# sw_receive.net
KiCad netlist of a schematic drawn in Altium Designer
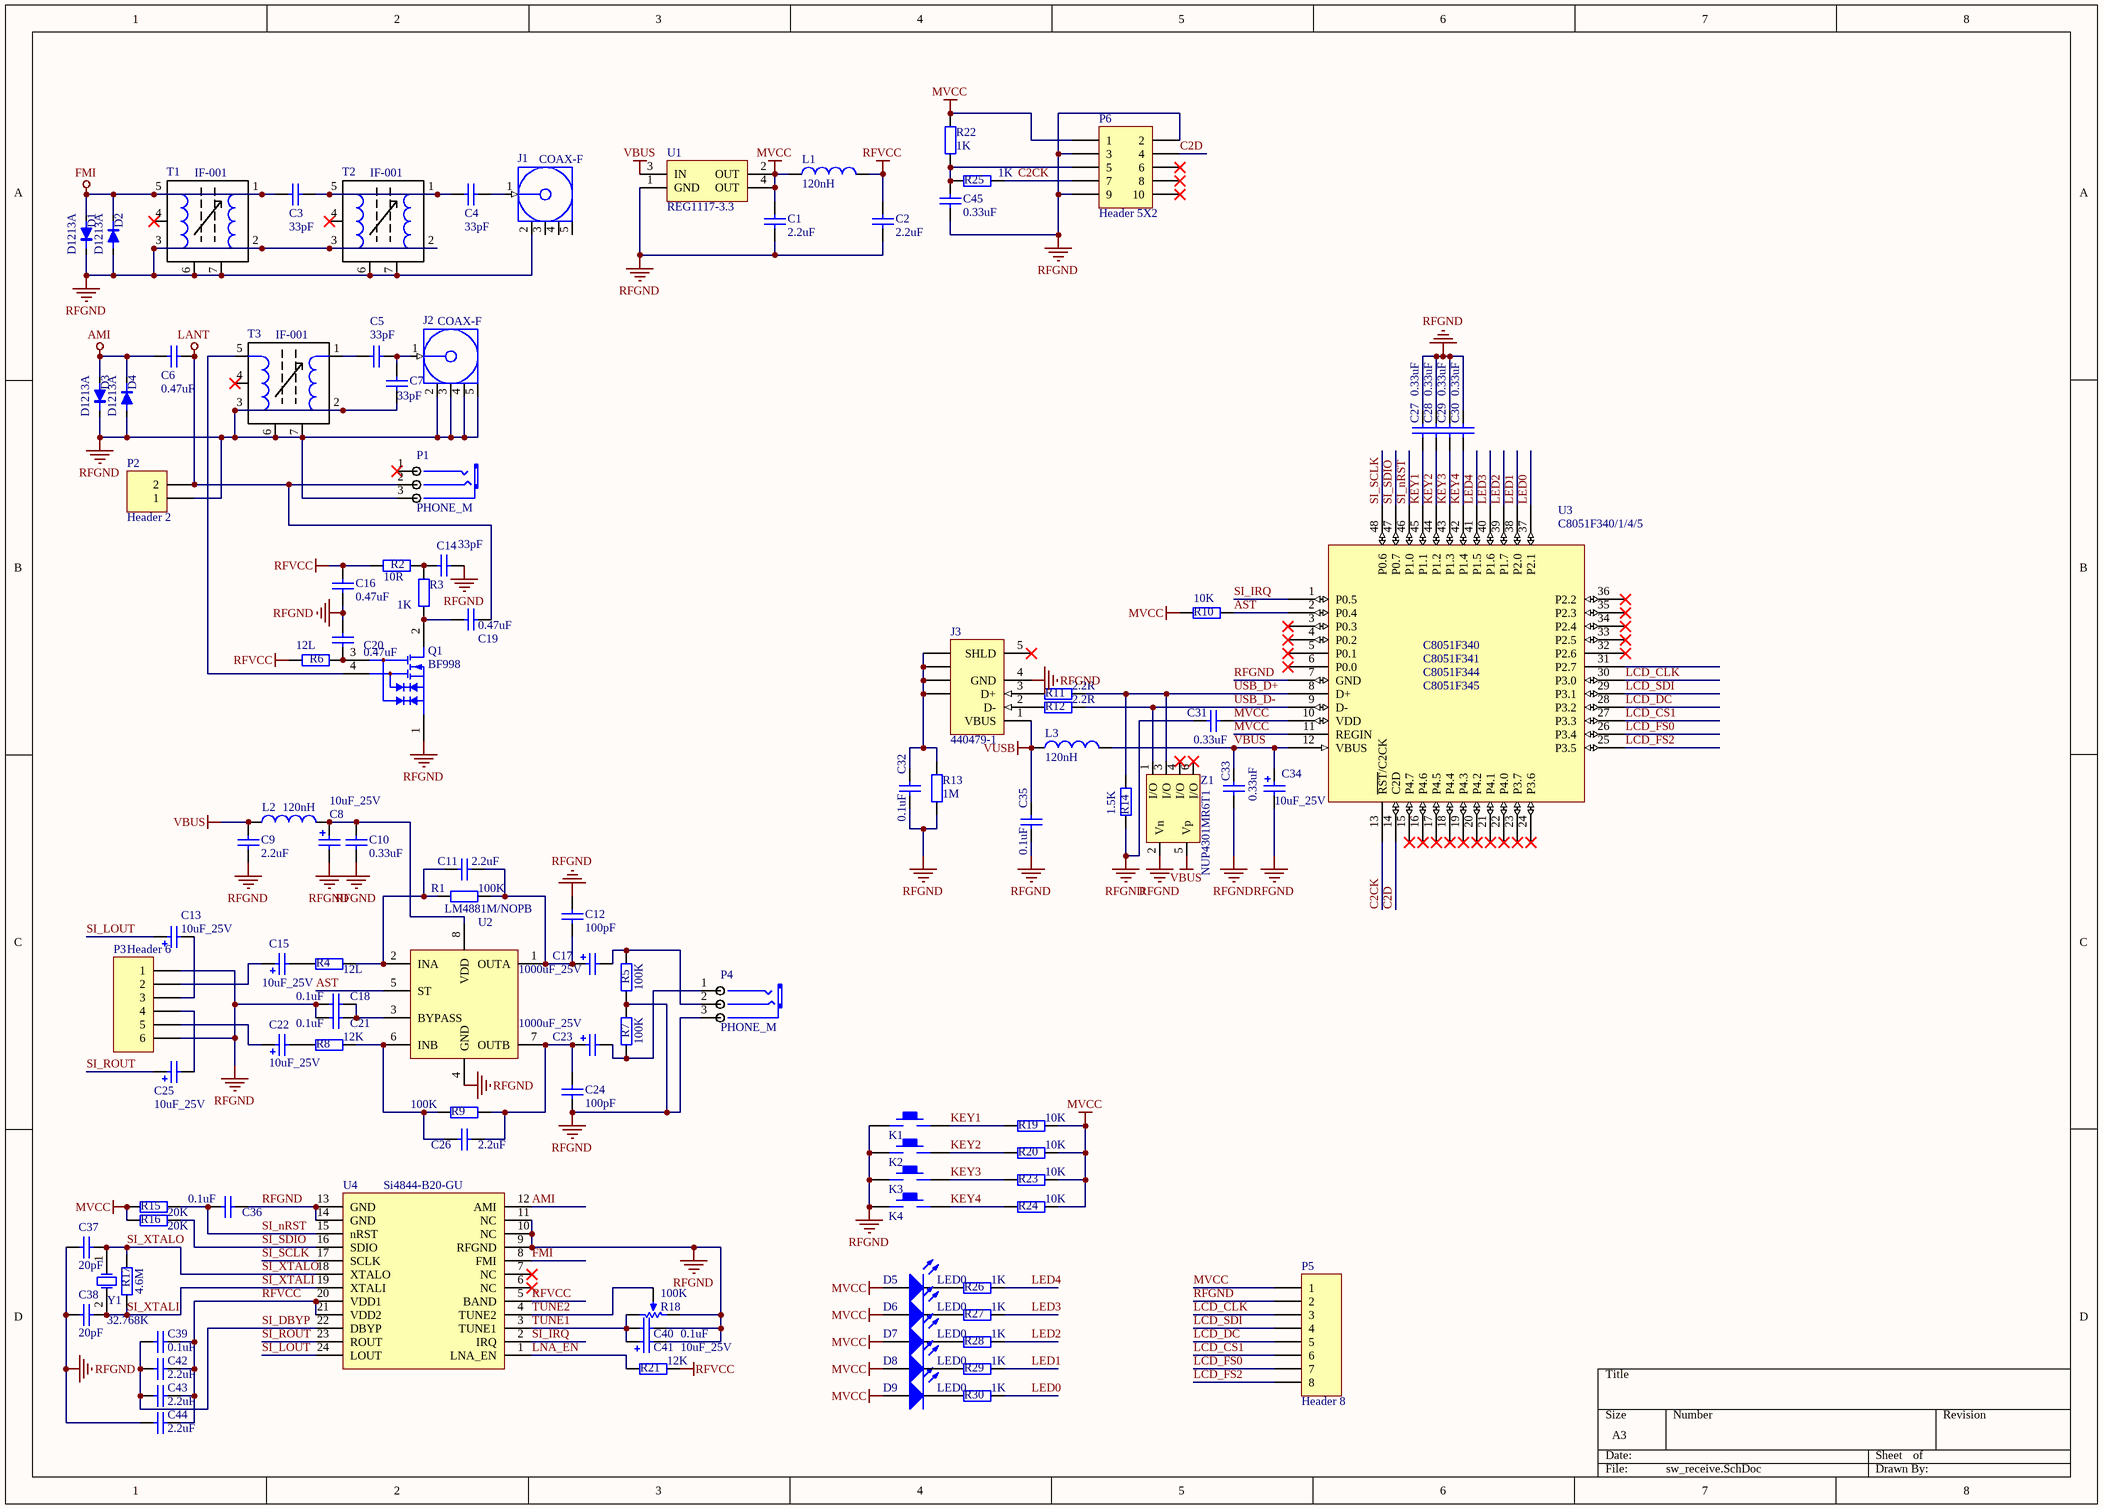
[diagram p0: sw_receive.SchDoc]

(export (version "E")
  (design (tool "Eeschema 10.0.6"))
  (components
    (comp (ref "C1")
      (value "2.2uF")
      (footprint "0805C")
      (description "Capacitor")
      (fields (field (name "PUBLISHER") "Altium Limited"))
      (libsource (lib "Miscellaneous Devices") (part "Cap"))
    )
    (comp (ref "C2")
      (value "2.2uF")
      (footprint "0805C")
      (description "Capacitor")
      (fields (field (name "PUBLISHER") "Altium Limited"))
      (libsource (lib "Miscellaneous Devices") (part "Cap"))
    )
    (comp (ref "C3")
      (value "33pF")
      (footprint "0805C")
      (description "Capacitor")
      (fields (field (name "PUBLISHER") "Altium Limited"))
      (libsource (lib "Miscellaneous Devices") (part "Cap"))
    )
    (comp (ref "C4")
      (value "33pF")
      (footprint "0805C")
      (description "Capacitor")
      (fields (field (name "PUBLISHER") "Altium Limited"))
      (libsource (lib "Miscellaneous Devices") (part "Cap"))
    )
    (comp (ref "C5")
      (value "33pF")
      (footprint "0805C")
      (description "Capacitor")
      (fields (field (name "PUBLISHER") "Altium Limited"))
      (libsource (lib "Miscellaneous Devices") (part "Cap"))
    )
    (comp (ref "C6")
      (value "0.47uF")
      (footprint "0805C")
      (description "Capacitor")
      (fields (field (name "PUBLISHER") "Altium Limited"))
      (libsource (lib "Miscellaneous Devices") (part "Cap"))
    )
    (comp (ref "C7")
      (value "33pF")
      (footprint "0805C")
      (description "Capacitor")
      (fields (field (name "PUBLISHER") "Altium Limited"))
      (libsource (lib "Miscellaneous Devices") (part "Cap"))
    )
    (comp (ref "C8")
      (value "10uF_25V")
      (footprint "RB2.5-6.3")
      (description "Polarized Capacitor (Axial)")
      (fields (field (name "PUBLISHER") "Altium Limited"))
      (libsource (lib "") (part "Cap Pol2_1"))
    )
    (comp (ref "C9")
      (value "2.2uF")
      (footprint "0805C")
      (description "Capacitor")
      (fields (field (name "PUBLISHER") "Altium Limited"))
      (libsource (lib "Miscellaneous Devices") (part "Cap"))
    )
    (comp (ref "C10")
      (value "0.33uF")
      (footprint "0805C")
      (description "Capacitor")
      (fields (field (name "PUBLISHER") "Altium Limited"))
      (libsource (lib "Miscellaneous Devices") (part "Cap"))
    )
    (comp (ref "C11")
      (value "2.2uF")
      (footprint "0805C")
      (description "Capacitor")
      (fields (field (name "PUBLISHER") "Altium Limited"))
      (libsource (lib "Miscellaneous Devices") (part "Cap"))
    )
    (comp (ref "C12")
      (value "100pF")
      (footprint "0805C")
      (description "Capacitor")
      (fields (field (name "PUBLISHER") "Altium Limited"))
      (libsource (lib "Miscellaneous Devices") (part "Cap"))
    )
    (comp (ref "C13")
      (value "10uF_25V")
      (footprint "RB2-5")
      (description "Polarized Capacitor (Axial)")
      (fields (field (name "PUBLISHER") "Altium Limited"))
      (libsource (lib "Miscellaneous Devices") (part "Cap Pol2"))
    )
    (comp (ref "C14")
      (value "33pF")
      (footprint "0805C")
      (description "Capacitor")
      (fields (field (name "PUBLISHER") "Altium Limited"))
      (libsource (lib "Miscellaneous Devices") (part "Cap"))
    )
    (comp (ref "C15")
      (value "10uF_25V")
      (footprint "RB2-5")
      (description "Polarized Capacitor (Axial)")
      (fields (field (name "PUBLISHER") "Altium Limited"))
      (libsource (lib "Miscellaneous Devices") (part "Cap Pol2"))
    )
    (comp (ref "C16")
      (value "0.47uF")
      (footprint "0805C")
      (description "Capacitor")
      (fields (field (name "PUBLISHER") "Altium Limited"))
      (libsource (lib "Miscellaneous Devices") (part "Cap"))
    )
    (comp (ref "C17")
      (value "1000uF_25V")
      (footprint "RB3.5-8")
      (description "Polarized Capacitor (Axial)")
      (fields (field (name "PUBLISHER") "Altium Limited"))
      (libsource (lib "Miscellaneous Devices") (part "Cap Pol2"))
    )
    (comp (ref "C18")
      (value "0.1uF")
      (footprint "CAPC3225L")
      (description "Capacitor")
      (fields (field (name "PUBLISHER") "Altium Limited"))
      (libsource (lib "Miscellaneous Devices") (part "Cap"))
    )
    (comp (ref "C19")
      (value "0.47uF")
      (footprint "0805C")
      (description "Capacitor")
      (fields (field (name "PUBLISHER") "Altium Limited"))
      (libsource (lib "Miscellaneous Devices") (part "Cap"))
    )
    (comp (ref "C20")
      (value "0.47uF")
      (footprint "0805C")
      (description "Capacitor")
      (fields (field (name "PUBLISHER") "Altium Limited"))
      (libsource (lib "Miscellaneous Devices") (part "Cap"))
    )
    (comp (ref "C21")
      (value "0.1uF")
      (footprint "0805C")
      (description "Capacitor")
      (fields (field (name "PUBLISHER") "Altium Limited"))
      (libsource (lib "Miscellaneous Devices") (part "Cap"))
    )
    (comp (ref "C22")
      (value "10uF_25V")
      (footprint "RB2-5")
      (description "Polarized Capacitor (Axial)")
      (fields (field (name "PUBLISHER") "Altium Limited"))
      (libsource (lib "Miscellaneous Devices") (part "Cap Pol2"))
    )
    (comp (ref "C23")
      (value "1000uF_25V")
      (footprint "RB3.5-8")
      (description "Polarized Capacitor (Axial)")
      (fields (field (name "PUBLISHER") "Altium Limited"))
      (libsource (lib "Miscellaneous Devices") (part "Cap Pol2"))
    )
    (comp (ref "C24")
      (value "100pF")
      (footprint "0805C")
      (description "Capacitor")
      (fields (field (name "PUBLISHER") "Altium Limited"))
      (libsource (lib "Miscellaneous Devices") (part "Cap"))
    )
    (comp (ref "C25")
      (value "10uF_25V")
      (footprint "RB2-5")
      (description "Polarized Capacitor (Axial)")
      (fields (field (name "PUBLISHER") "Altium Limited"))
      (libsource (lib "Miscellaneous Devices") (part "Cap Pol2"))
    )
    (comp (ref "C26")
      (value "2.2uF")
      (footprint "0805C")
      (description "Capacitor")
      (fields (field (name "PUBLISHER") "Altium Limited"))
      (libsource (lib "Miscellaneous Devices") (part "Cap"))
    )
    (comp (ref "C27")
      (value "0.33uF")
      (footprint "0805C")
      (description "Capacitor")
      (fields (field (name "PUBLISHER") "Altium Limited"))
      (libsource (lib "Miscellaneous Devices") (part "Cap"))
    )
    (comp (ref "C28")
      (value "0.33uF")
      (footprint "0805C")
      (description "Capacitor")
      (fields (field (name "PUBLISHER") "Altium Limited"))
      (libsource (lib "Miscellaneous Devices") (part "Cap"))
    )
    (comp (ref "C29")
      (value "0.33uF")
      (footprint "0805C")
      (description "Capacitor")
      (fields (field (name "PUBLISHER") "Altium Limited"))
      (libsource (lib "Miscellaneous Devices") (part "Cap"))
    )
    (comp (ref "C30")
      (value "0.33uF")
      (footprint "0805C")
      (description "Capacitor")
      (fields (field (name "PUBLISHER") "Altium Limited"))
      (libsource (lib "Miscellaneous Devices") (part "Cap"))
    )
    (comp (ref "C31")
      (value "0.33uF")
      (footprint "0805C")
      (description "Capacitor")
      (fields (field (name "PUBLISHER") "Altium Limited"))
      (libsource (lib "Miscellaneous Devices") (part "Cap"))
    )
    (comp (ref "C32")
      (value "0.1uF")
      (footprint "0805C")
      (description "Capacitor")
      (fields (field (name "PUBLISHER") "Altium Limited"))
      (libsource (lib "Miscellaneous Devices") (part "Cap"))
    )
    (comp (ref "C33")
      (value "0.33uF")
      (footprint "0805C")
      (description "Capacitor")
      (fields (field (name "PUBLISHER") "Altium Limited"))
      (libsource (lib "Miscellaneous Devices") (part "Cap"))
    )
    (comp (ref "C34")
      (value "10uF_25V")
      (footprint "RB2.5-6.3")
      (description "Polarized Capacitor (Axial)")
      (fields (field (name "PUBLISHER") "Altium Limited"))
      (libsource (lib "") (part "Cap Pol2_1"))
    )
    (comp (ref "C35")
      (value "0.1uF")
      (footprint "0805C")
      (description "Capacitor")
      (fields (field (name "PUBLISHER") "Altium Limited"))
      (libsource (lib "Miscellaneous Devices") (part "Cap"))
    )
    (comp (ref "C36")
      (value "0.1uF")
      (footprint "0805C")
      (description "Capacitor")
      (fields (field (name "PUBLISHER") "Altium Limited"))
      (libsource (lib "Miscellaneous Devices") (part "Cap"))
    )
    (comp (ref "C37")
      (value "20pF")
      (footprint "0805C")
      (description "Capacitor")
      (fields (field (name "PUBLISHER") "Altium Limited"))
      (libsource (lib "Miscellaneous Devices") (part "Cap"))
    )
    (comp (ref "C38")
      (value "20pF")
      (footprint "0805C")
      (description "Capacitor")
      (fields (field (name "PUBLISHER") "Altium Limited"))
      (libsource (lib "Miscellaneous Devices") (part "Cap"))
    )
    (comp (ref "C39")
      (value "0.1uF")
      (footprint "0805C")
      (description "Capacitor")
      (fields (field (name "PUBLISHER") "Altium Limited"))
      (libsource (lib "Miscellaneous Devices") (part "Cap"))
    )
    (comp (ref "C40")
      (value "0.1uF")
      (footprint "0805C")
      (description "Capacitor")
      (fields (field (name "PUBLISHER") "Altium Limited"))
      (libsource (lib "Miscellaneous Devices") (part "Cap"))
    )
    (comp (ref "C41")
      (value "10uF_25V")
      (footprint "RB2.5-6.3")
      (description "Polarized Capacitor (Axial)")
      (fields (field (name "PUBLISHER") "Altium Limited"))
      (libsource (lib "Miscellaneous Devices") (part "Cap Pol2"))
    )
    (comp (ref "C42")
      (value "2.2uF")
      (footprint "CAPC3225L")
      (description "Capacitor")
      (fields (field (name "PUBLISHER") "Altium Limited"))
      (libsource (lib "Miscellaneous Devices") (part "Cap"))
    )
    (comp (ref "C43")
      (value "2.2uF")
      (footprint "CAPC3225L")
      (description "Capacitor")
      (fields (field (name "PUBLISHER") "Altium Limited"))
      (libsource (lib "Miscellaneous Devices") (part "Cap"))
    )
    (comp (ref "C44")
      (value "2.2uF")
      (footprint "CAPC3225L")
      (description "Capacitor")
      (fields (field (name "PUBLISHER") "Altium Limited"))
      (libsource (lib "Miscellaneous Devices") (part "Cap"))
    )
    (comp (ref "C45")
      (value "0.33uF")
      (footprint "0805C")
      (description "Capacitor")
      (fields (field (name "PUBLISHER") "Altium Limited"))
      (libsource (lib "Miscellaneous Devices") (part "Cap"))
    )
    (comp (ref "D1") (value "D1213A") (footprint "SOD-323") (libsource (lib "常用元件库") (part "DIODE1")))
    (comp (ref "D2") (value "D1213A") (footprint "SOD-323") (libsource (lib "常用元件库") (part "DIODE1")))
    (comp (ref "D3") (value "D1213A") (footprint "SOD-323") (libsource (lib "常用元件库") (part "DIODE1")))
    (comp (ref "D4") (value "D1213A") (footprint "SOD-323") (libsource (lib "常用元件库") (part "DIODE1")))
    (comp (ref "D5")
      (value "LED0")
      (footprint "LEDLight")
      (description "Typical INFRARED GaAs LED")
      (fields (field (name "PUBLISHER") "Altium Limited"))
      (libsource (lib "Miscellaneous Devices") (part "LED0"))
    )
    (comp (ref "D6")
      (value "LED0")
      (footprint "LEDLight")
      (description "Typical INFRARED GaAs LED")
      (fields (field (name "PUBLISHER") "Altium Limited"))
      (libsource (lib "Miscellaneous Devices") (part "LED0"))
    )
    (comp (ref "D7")
      (value "LED0")
      (footprint "LEDLight")
      (description "Typical INFRARED GaAs LED")
      (fields (field (name "PUBLISHER") "Altium Limited"))
      (libsource (lib "Miscellaneous Devices") (part "LED0"))
    )
    (comp (ref "D8")
      (value "LED0")
      (footprint "LEDLight")
      (description "Typical INFRARED GaAs LED")
      (fields (field (name "PUBLISHER") "Altium Limited"))
      (libsource (lib "Miscellaneous Devices") (part "LED0"))
    )
    (comp (ref "D9")
      (value "LED0")
      (footprint "LEDLight")
      (description "Typical INFRARED GaAs LED")
      (fields (field (name "PUBLISHER") "Altium Limited"))
      (libsource (lib "Miscellaneous Devices") (part "LED0"))
    )
    (comp (ref "J1")
      (value "COAX-F")
      (footprint "MCX5.08-H5")
      (fields (field (name "PUBLISHER") "Altium Limited"))
      (libsource (lib "Miscellaneous Connectors") (part "COAX-F"))
    )
    (comp (ref "J2")
      (value "COAX-F")
      (footprint "MCX5.08-H5")
      (fields (field (name "PUBLISHER") "Altium Limited"))
      (libsource (lib "Miscellaneous Connectors") (part "COAX-F"))
    )
    (comp (ref "J3")
      (value "440479-1")
      (footprint "440479")
      (description "USB 2.0, Right Angle, SMT, AB Type, Receptacle, 5 Position, Black")
      (fields (field (name "PUBLISHER") "Altium Limited"))
      (libsource (lib "AMP Serial Bus USB") (part "440479-1"))
    )
    (comp (ref "K1") (value "KEY_M") (footprint "KEY_M") (libsource (lib "战舰STM32开发板底板封装库") (part "KEY_M")))
    (comp (ref "K2") (value "KEY_M") (footprint "KEY_M") (libsource (lib "战舰STM32开发板底板封装库") (part "KEY_M")))
    (comp (ref "K3") (value "KEY_M") (footprint "KEY_M") (libsource (lib "战舰STM32开发板底板封装库") (part "KEY_M")))
    (comp (ref "K4") (value "KEY_M") (footprint "KEY_M") (libsource (lib "战舰STM32开发板底板封装库") (part "KEY_M")))
    (comp (ref "L1")
      (value "120nH")
      (footprint "0805R")
      (description "Inductor")
      (fields (field (name "PUBLISHER") "Altium Limited"))
      (libsource (lib "Miscellaneous Devices") (part "Inductor"))
    )
    (comp (ref "L2")
      (value "120nH")
      (footprint "0805R")
      (description "Inductor")
      (fields (field (name "PUBLISHER") "Altium Limited"))
      (libsource (lib "Miscellaneous Devices") (part "Inductor"))
    )
    (comp (ref "L3")
      (value "120nH")
      (footprint "3225[1210]")
      (description "Inductor")
      (fields (field (name "PUBLISHER") "Altium Limited"))
      (libsource (lib "Miscellaneous Devices") (part "Inductor"))
    )
    (comp (ref "P1")
      (value "PHONE_M")
      (footprint "PHONE_ST")
      (libsource (lib "战舰STM32开发板底板封装库") (part "PHONE_M"))
    )
    (comp (ref "P2")
      (value "Header 2")
      (footprint "2510-2")
      (description "Header, 2-Pin")
      (fields (field (name "PUBLISHER") "Altium Limited"))
      (libsource (lib "Miscellaneous Connectors") (part "Header 2"))
    )
    (comp (ref "P3")
      (value "Header 6")
      (footprint "RK097")
      (description "Header, 6-Pin")
      (fields (field (name "PUBLISHER") "Altium Limited"))
      (libsource (lib "Miscellaneous Connectors") (part "Header 6"))
    )
    (comp (ref "P4")
      (value "PHONE_M")
      (footprint "PHONE_ST")
      (libsource (lib "战舰STM32开发板底板封装库") (part "PHONE_M"))
    )
    (comp (ref "P5")
      (value "Header 8")
      (footprint "HDR1X8")
      (description "Header, 8-Pin")
      (fields (field (name "PUBLISHER") "Altium Limited"))
      (libsource (lib "Miscellaneous Connectors") (part "Header 8"))
    )
    (comp (ref "P6")
      (value "Header 5X2")
      (footprint "FKV10SN")
      (description "Header, 5-Pin, Dual row")
      (fields (field (name "PUBLISHER") "Altium Limited"))
      (libsource (lib "Miscellaneous Connectors") (part "Header 5X2"))
    )
    (comp (ref "Q1")
      (value "BF998")
      (footprint "SOT143")
      (description "Silicon N-channel Dual-gate MOSFET")
      (fields (field (name "PUBLISHER") "Altium Limited"))
      (libsource (lib "Philips Discrete MOSFET - Low Power") (part "BF998"))
    )
    (comp (ref "R1")
      (value "100K")
      (footprint "0805R")
      (description "Resistor")
      (fields (field (name "PUBLISHER") "Altium Limited"))
      (libsource (lib "") (part "Res2_2"))
    )
    (comp (ref "R2")
      (value "10R")
      (footprint "0805R")
      (description "Resistor")
      (fields (field (name "PUBLISHER") "Altium Limited"))
      (libsource (lib "") (part "Res2_1"))
    )
    (comp (ref "R3")
      (value "1K")
      (footprint "0805R")
      (description "Resistor")
      (fields (field (name "PUBLISHER") "Altium Limited"))
      (libsource (lib "Miscellaneous Devices") (part "Res2"))
    )
    (comp (ref "R4")
      (value "12L")
      (footprint "0805R")
      (description "Resistor")
      (fields (field (name "PUBLISHER") "Altium Limited"))
      (libsource (lib "") (part "Res2_2"))
    )
    (comp (ref "R5")
      (value "100K")
      (footprint "0805R")
      (description "Resistor")
      (fields (field (name "PUBLISHER") "Altium Limited"))
      (libsource (lib "") (part "Res2_1"))
    )
    (comp (ref "R6")
      (value "12L")
      (footprint "0805R")
      (description "Resistor")
      (fields (field (name "PUBLISHER") "Altium Limited"))
      (libsource (lib "") (part "Res2_1"))
    )
    (comp (ref "R7")
      (value "100K")
      (footprint "0805R")
      (description "Resistor")
      (fields (field (name "PUBLISHER") "Altium Limited"))
      (libsource (lib "Miscellaneous Devices") (part "Res2"))
    )
    (comp (ref "R8")
      (value "12K")
      (footprint "0805R")
      (description "Resistor")
      (fields (field (name "PUBLISHER") "Altium Limited"))
      (libsource (lib "") (part "Res2_2"))
    )
    (comp (ref "R9")
      (value "100K")
      (footprint "0805R")
      (description "Resistor")
      (fields (field (name "PUBLISHER") "Altium Limited"))
      (libsource (lib "") (part "Res2_1"))
    )
    (comp (ref "R10")
      (value "10K")
      (footprint "0805R")
      (description "Resistor")
      (fields (field (name "PUBLISHER") "Altium Limited"))
      (libsource (lib "") (part "Res2_2"))
    )
    (comp (ref "R11")
      (value "2.2R")
      (footprint "0805R")
      (description "Resistor")
      (fields (field (name "PUBLISHER") "Altium Limited"))
      (libsource (lib "") (part "Res2_2"))
    )
    (comp (ref "R12")
      (value "2.2R")
      (footprint "0805R")
      (description "Resistor")
      (fields (field (name "PUBLISHER") "Altium Limited"))
      (libsource (lib "") (part "Res2_2"))
    )
    (comp (ref "R13")
      (value "1M")
      (footprint "0805R")
      (description "Resistor")
      (fields (field (name "PUBLISHER") "Altium Limited"))
      (libsource (lib "Miscellaneous Devices") (part "Res2"))
    )
    (comp (ref "R14")
      (value "1.5K")
      (footprint "0805R")
      (description "Resistor")
      (fields (field (name "PUBLISHER") "Altium Limited"))
      (libsource (lib "Miscellaneous Devices") (part "Res2"))
    )
    (comp (ref "R15")
      (value "20K")
      (footprint "0805R")
      (description "Resistor")
      (fields (field (name "PUBLISHER") "Altium Limited"))
      (libsource (lib "") (part "Res2_2"))
    )
    (comp (ref "R16")
      (value "20K")
      (footprint "0805R")
      (description "Resistor")
      (fields (field (name "PUBLISHER") "Altium Limited"))
      (libsource (lib "") (part "Res2_2"))
    )
    (comp (ref "R17")
      (value "4.6M")
      (footprint "0805R")
      (description "Resistor")
      (fields (field (name "PUBLISHER") "Altium Limited"))
      (libsource (lib "Miscellaneous Devices") (part "Res2"))
    )
    (comp (ref "R18")
      (value "100K")
      (footprint "3590S")
      (description "Potentiometer")
      (fields (field (name "PUBLISHER") "Altium Limited"))
      (libsource (lib "Miscellaneous Devices") (part "RPot"))
    )
    (comp (ref "R19")
      (value "10K")
      (footprint "0805R")
      (description "Resistor")
      (fields (field (name "PUBLISHER") "Altium Limited"))
      (libsource (lib "") (part "Res2_2"))
    )
    (comp (ref "R20")
      (value "10K")
      (footprint "0805R")
      (description "Resistor")
      (fields (field (name "PUBLISHER") "Altium Limited"))
      (libsource (lib "") (part "Res2_2"))
    )
    (comp (ref "R21")
      (value "12K")
      (footprint "0805R")
      (description "Resistor")
      (fields (field (name "PUBLISHER") "Altium Limited"))
      (libsource (lib "") (part "Res2_2"))
    )
    (comp (ref "R22")
      (value "1K")
      (footprint "0805R")
      (description "Resistor")
      (fields (field (name "PUBLISHER") "Altium Limited"))
      (libsource (lib "Miscellaneous Devices") (part "Res2"))
    )
    (comp (ref "R23")
      (value "10K")
      (footprint "0805R")
      (description "Resistor")
      (fields (field (name "PUBLISHER") "Altium Limited"))
      (libsource (lib "") (part "Res2_2"))
    )
    (comp (ref "R24")
      (value "10K")
      (footprint "0805R")
      (description "Resistor")
      (fields (field (name "PUBLISHER") "Altium Limited"))
      (libsource (lib "") (part "Res2_2"))
    )
    (comp (ref "R25")
      (value "1K")
      (footprint "0805R")
      (description "Resistor")
      (fields (field (name "PUBLISHER") "Altium Limited"))
      (libsource (lib "") (part "Res2_2"))
    )
    (comp (ref "R26")
      (value "1K")
      (footprint "0805R")
      (description "Resistor")
      (fields (field (name "PUBLISHER") "Altium Limited"))
      (libsource (lib "") (part "Res2_1"))
    )
    (comp (ref "R27")
      (value "1K")
      (footprint "0805R")
      (description "Resistor")
      (fields (field (name "PUBLISHER") "Altium Limited"))
      (libsource (lib "") (part "Res2_1"))
    )
    (comp (ref "R28")
      (value "1K")
      (footprint "0805R")
      (description "Resistor")
      (fields (field (name "PUBLISHER") "Altium Limited"))
      (libsource (lib "") (part "Res2_1"))
    )
    (comp (ref "R29")
      (value "1K")
      (footprint "0805R")
      (description "Resistor")
      (fields (field (name "PUBLISHER") "Altium Limited"))
      (libsource (lib "") (part "Res2_1"))
    )
    (comp (ref "R30")
      (value "1K")
      (footprint "0805R")
      (description "Resistor")
      (fields (field (name "PUBLISHER") "Altium Limited"))
      (libsource (lib "") (part "Res2_1"))
    )
    (comp (ref "T1") (value "IF-001") (footprint "IF_10X10") (libsource (lib "IFT") (part "IF-001")))
    (comp (ref "T2") (value "IF-001") (footprint "IF_10X10") (libsource (lib "IFT") (part "IF-001")))
    (comp (ref "T3") (value "IF-001") (footprint "IF_10X10") (libsource (lib "IFT") (part "IF-001")))
    (comp (ref "U1")
      (value "REG1117-3.3")
      (footprint "ZZ311")
      (description "800mA and 1A Low Dropout Positive Regulator 2.85V, 3.3V, 5V, and Adjustable")
      (fields (field (name "PUBLISHER") "Altium Limited"))
      (libsource (lib "BB Power Mgt Voltage Regulator") (part "REG1117-3.3"))
    )
    (comp (ref "U2")
      (value "LM4881M/NOPB")
      (footprint "SO-8")
      (libsource (lib "LM4881M") (part "LM4881M/NOPB"))
    )
    (comp (ref "U3")
      (value "C8051F340/1/4/5")
      (footprint "TQFP-48")
      (libsource (lib "CYGNALsch") (part "C8051F340/1/4/5"))
    )
    (comp (ref "U4")
      (value "Si4844-B20-GU")
      (footprint "SSOP24-0.635")
      (description "模拟调谐数字显示 AM/FM/SW 收音机")
      (libsource (lib "si4844B20") (part "Si4844-B20-GU"))
    )
    (comp (ref "Y1")
      (value "32.768K")
      (footprint "Crystal32")
      (description "Crystal Oscillator")
      (fields (field (name "PUBLISHER") "Altium Limited"))
      (libsource (lib "Miscellaneous Devices") (part "XTAL"))
    )
    (comp (ref "Z1")
      (value "NUP4301MR6T1")
      (footprint "TSOP-6")
      (description "ESD protection")
      (libsource (lib "常用原理图库") (part "NUP4301MR6T1"))
    )
  )
  (nets
    (net (code "1") (name "/AST") (class "Default")
      (node (ref "R10") (pin "2") (pinfunction "2_2") (pintype "passive"))
      (node (ref "U2") (pin "5") (pinfunction "ST_5") (pintype "passive"))
      (node (ref "U3") (pin "2") (pinfunction "P0.4_2") (pintype "bidirectional"))
    )
    (net (code "2") (name "/C2CK") (class "Default")
      (node (ref "P6") (pin "7") (pinfunction "7_7") (pintype "passive"))
      (node (ref "R25") (pin "2") (pinfunction "2_2") (pintype "passive"))
      (node (ref "U3") (pin "13") (pinfunction "~{RST}/C2CK_13") (pintype "power_in"))
    )
    (net (code "3") (name "/C2D") (class "Default")
      (node (ref "P6") (pin "4") (pinfunction "4_4") (pintype "passive"))
      (node (ref "U3") (pin "14") (pinfunction "C2D_14") (pintype "bidirectional"))
    )
    (net (code "4") (name "/KEY1") (class "Default")
      (node (ref "C27") (pin "2") (pinfunction "2_2") (pintype "passive"))
      (node (ref "K1") (pin "2") (pinfunction "2_2") (pintype "passive"))
      (node (ref "R19") (pin "1") (pinfunction "1_1") (pintype "passive"))
      (node (ref "U3") (pin "45") (pinfunction "P1.1_45") (pintype "bidirectional"))
    )
    (net (code "5") (name "/KEY2") (class "Default")
      (node (ref "C28") (pin "2") (pinfunction "2_2") (pintype "passive"))
      (node (ref "K2") (pin "2") (pinfunction "2_2") (pintype "passive"))
      (node (ref "R20") (pin "1") (pinfunction "1_1") (pintype "passive"))
      (node (ref "U3") (pin "44") (pinfunction "P1.2_44") (pintype "bidirectional"))
    )
    (net (code "6") (name "/KEY3") (class "Default")
      (node (ref "C29") (pin "2") (pinfunction "2_2") (pintype "passive"))
      (node (ref "K3") (pin "2") (pinfunction "2_2") (pintype "passive"))
      (node (ref "R23") (pin "1") (pinfunction "1_1") (pintype "passive"))
      (node (ref "U3") (pin "43") (pinfunction "P1.3_43") (pintype "bidirectional"))
    )
    (net (code "7") (name "/KEY4") (class "Default")
      (node (ref "C30") (pin "2") (pinfunction "2_2") (pintype "passive"))
      (node (ref "K4") (pin "2") (pinfunction "2_2") (pintype "passive"))
      (node (ref "R24") (pin "1") (pinfunction "1_1") (pintype "passive"))
      (node (ref "U3") (pin "42") (pinfunction "P1.4_42") (pintype "bidirectional"))
    )
    (net (code "8") (name "/LCD_CLK") (class "Default")
      (node (ref "P5") (pin "3") (pinfunction "3_3") (pintype "passive"))
      (node (ref "U3") (pin "30") (pinfunction "P3.0_30") (pintype "bidirectional"))
    )
    (net (code "9") (name "/LCD_CS1") (class "Default")
      (node (ref "P5") (pin "6") (pinfunction "6_6") (pintype "passive"))
      (node (ref "U3") (pin "27") (pinfunction "P3.3_27") (pintype "bidirectional"))
    )
    (net (code "10") (name "/LCD_DC") (class "Default")
      (node (ref "P5") (pin "5") (pinfunction "5_5") (pintype "passive"))
      (node (ref "U3") (pin "28") (pinfunction "P3.2_28") (pintype "bidirectional"))
    )
    (net (code "11") (name "/LCD_FS0") (class "Default")
      (node (ref "P5") (pin "7") (pinfunction "7_7") (pintype "passive"))
      (node (ref "U3") (pin "26") (pinfunction "P3.4_26") (pintype "bidirectional"))
    )
    (net (code "12") (name "/LCD_FS2") (class "Default")
      (node (ref "P5") (pin "8") (pinfunction "8_8") (pintype "passive"))
      (node (ref "U3") (pin "25") (pinfunction "P3.5_25") (pintype "bidirectional"))
    )
    (net (code "13") (name "/LCD_SDI") (class "Default")
      (node (ref "P5") (pin "4") (pinfunction "4_4") (pintype "passive"))
      (node (ref "U3") (pin "29") (pinfunction "P3.1_29") (pintype "bidirectional"))
    )
    (net (code "14") (name "/LED0") (class "Default")
      (node (ref "R30") (pin "1") (pinfunction "1_1") (pintype "passive"))
      (node (ref "U3") (pin "37") (pinfunction "P2.1_37") (pintype "bidirectional"))
    )
    (net (code "15") (name "/LED1") (class "Default")
      (node (ref "R29") (pin "1") (pinfunction "1_1") (pintype "passive"))
      (node (ref "U3") (pin "38") (pinfunction "P2.0_38") (pintype "bidirectional"))
    )
    (net (code "16") (name "/LED2") (class "Default")
      (node (ref "R28") (pin "1") (pinfunction "1_1") (pintype "passive"))
      (node (ref "U3") (pin "39") (pinfunction "P1.7_39") (pintype "bidirectional"))
    )
    (net (code "17") (name "/LED3") (class "Default")
      (node (ref "R27") (pin "1") (pinfunction "1_1") (pintype "passive"))
      (node (ref "U3") (pin "40") (pinfunction "P1.6_40") (pintype "bidirectional"))
    )
    (net (code "18") (name "/LED4") (class "Default")
      (node (ref "R26") (pin "1") (pinfunction "1_1") (pintype "passive"))
      (node (ref "U3") (pin "41") (pinfunction "P1.5_41") (pintype "bidirectional"))
    )
    (net (code "19") (name "/LNA_EN") (class "Default")
      (node (ref "R21") (pin "1") (pinfunction "1_1") (pintype "passive"))
      (node (ref "U4") (pin "1") (pinfunction "LNA_EN_1") (pintype "passive"))
    )
    (net (code "20") (name "/SI_DBYP") (class "Default")
      (node (ref "C39") (pin "1") (pinfunction "1_1") (pintype "passive"))
      (node (ref "C42") (pin "1") (pinfunction "1_1") (pintype "passive"))
      (node (ref "C43") (pin "1") (pinfunction "1_1") (pintype "passive"))
      (node (ref "U4") (pin "22") (pinfunction "DBYP_22") (pintype "passive"))
    )
    (net (code "21") (name "/SI_IRQ") (class "Default")
      (node (ref "U3") (pin "1") (pinfunction "P0.5_1") (pintype "bidirectional"))
      (node (ref "U4") (pin "2") (pinfunction "IRQ_2") (pintype "passive"))
    )
    (net (code "22") (name "/SI_LOUT") (class "Default")
      (node (ref "C13") (pin "1") (pinfunction "1_1") (pintype "passive"))
      (node (ref "U4") (pin "24") (pinfunction "LOUT_24") (pintype "passive"))
    )
    (net (code "23") (name "/SI_ROUT") (class "Default")
      (node (ref "C25") (pin "1") (pinfunction "1_1") (pintype "passive"))
      (node (ref "U4") (pin "23") (pinfunction "ROUT_23") (pintype "passive"))
    )
    (net (code "24") (name "/SI_SCLK") (class "Default")
      (node (ref "U3") (pin "48") (pinfunction "P0.6_48") (pintype "bidirectional"))
      (node (ref "U4") (pin "17") (pinfunction "SCLK_17") (pintype "passive"))
    )
    (net (code "25") (name "/SI_SDIO") (class "Default")
      (node (ref "R16") (pin "2") (pinfunction "2_2") (pintype "passive"))
      (node (ref "U3") (pin "47") (pinfunction "P0.7_47") (pintype "bidirectional"))
      (node (ref "U4") (pin "16") (pinfunction "SDIO_16") (pintype "passive"))
    )
    (net (code "26") (name "/SI_XTALI") (class "Default")
      (node (ref "C38") (pin "1") (pinfunction "1_1") (pintype "passive"))
      (node (ref "R17") (pin "1") (pinfunction "1_1") (pintype "passive"))
      (node (ref "U4") (pin "19") (pinfunction "XTALI_19") (pintype "passive"))
      (node (ref "Y1") (pin "2") (pinfunction "OSC2_2") (pintype "passive"))
    )
    (net (code "27") (name "/SI_XTALO") (class "Default")
      (node (ref "C37") (pin "1") (pinfunction "1_1") (pintype "passive"))
      (node (ref "R17") (pin "2") (pinfunction "2_2") (pintype "passive"))
      (node (ref "U4") (pin "18") (pinfunction "XTALO_18") (pintype "passive"))
      (node (ref "Y1") (pin "1") (pinfunction "OSC1_1") (pintype "passive"))
    )
    (net (code "28") (name "/SI_nRST") (class "Default")
      (node (ref "C36") (pin "1") (pinfunction "1_1") (pintype "passive"))
      (node (ref "R15") (pin "2") (pinfunction "2_2") (pintype "passive"))
      (node (ref "U3") (pin "46") (pinfunction "P1.0_46") (pintype "bidirectional"))
      (node (ref "U4") (pin "15") (pinfunction "nRST_15") (pintype "passive"))
    )
    (net (code "29") (name "/TUNE1") (class "Default")
      (node (ref "C40") (pin "1") (pinfunction "1_1") (pintype "passive"))
      (node (ref "C41") (pin "1") (pinfunction "1_1") (pintype "passive"))
      (node (ref "R18") (pin "1") (pinfunction "TOP_1") (pintype "passive"))
      (node (ref "U4") (pin "3") (pinfunction "TUNE1_3") (pintype "passive"))
    )
    (net (code "30") (name "/TUNE2") (class "Default")
      (node (ref "R18") (pin "3") (pinfunction "TAP_3") (pintype "passive"))
      (node (ref "U4") (pin "4") (pinfunction "TUNE2_4") (pintype "passive"))
    )
    (net (code "31") (name "/USB_D+") (class "Default")
      (node (ref "R11") (pin "2") (pinfunction "2_2") (pintype "passive"))
      (node (ref "R14") (pin "2") (pinfunction "2_2") (pintype "passive"))
      (node (ref "U3") (pin "8") (pinfunction "D+_8") (pintype "power_in"))
      (node (ref "Z1") (pin "3") (pinfunction "I/O_3") (pintype "power_in"))
    )
    (net (code "32") (name "/USB_D-") (class "Default")
      (node (ref "R12") (pin "2") (pinfunction "2_2") (pintype "passive"))
      (node (ref "U3") (pin "9") (pinfunction "D-_9") (pintype "bidirectional"))
      (node (ref "Z1") (pin "1") (pinfunction "I/O_1") (pintype "power_in"))
    )
    (net (code "33") (name "AMI") (class "Default")
      (node (ref "C6") (pin "1") (pinfunction "1_1") (pintype "passive"))
      (node (ref "D3") (pin "1") (pinfunction "A_1") (pintype "passive"))
      (node (ref "D4") (pin "2") (pinfunction "K_2") (pintype "passive"))
      (node (ref "U4") (pin "12") (pinfunction "AMI_12") (pintype "passive"))
    )
    (net (code "34") (name "FMI") (class "Default")
      (node (ref "C3") (pin "2") (pinfunction "2_2") (pintype "passive"))
      (node (ref "D1") (pin "1") (pinfunction "A_1") (pintype "passive"))
      (node (ref "D2") (pin "2") (pinfunction "K_2") (pintype "passive"))
      (node (ref "T1") (pin "1") (pinfunction "1_1") (pintype "passive"))
      (node (ref "T1") (pin "5") (pinfunction "5_5") (pintype "passive"))
      (node (ref "U4") (pin "8") (pinfunction "FMI_8") (pintype "passive"))
    )
    (net (code "35") (name "LANT") (class "Default")
      (node (ref "C19") (pin "1") (pinfunction "1_1") (pintype "passive"))
      (node (ref "C6") (pin "2") (pinfunction "2_2") (pintype "passive"))
      (node (ref "P1") (pin "2") (pinfunction "CHR_2") (pintype "passive"))
      (node (ref "P2") (pin "2") (pinfunction "2_2") (pintype "passive"))
    )
    (net (code "36") (name "MVCC") (class "Default")
      (node (ref "C1") (pin "2") (pinfunction "2_2") (pintype "passive"))
      (node (ref "C31") (pin "1") (pinfunction "1_1") (pintype "passive"))
      (node (ref "D5") (pin "1") (pinfunction "A_1") (pintype "passive"))
      (node (ref "D6") (pin "1") (pinfunction "A_1") (pintype "passive"))
      (node (ref "D7") (pin "1") (pinfunction "A_1") (pintype "passive"))
      (node (ref "D8") (pin "1") (pinfunction "A_1") (pintype "passive"))
      (node (ref "D9") (pin "1") (pinfunction "A_1") (pintype "passive"))
      (node (ref "L1") (pin "1") (pinfunction "1_1") (pintype "passive"))
      (node (ref "P5") (pin "1") (pinfunction "1_1") (pintype "passive"))
      (node (ref "P6") (pin "1") (pinfunction "1_1") (pintype "passive"))
      (node (ref "R10") (pin "1") (pinfunction "1_1") (pintype "passive"))
      (node (ref "R15") (pin "1") (pinfunction "1_1") (pintype "passive"))
      (node (ref "R16") (pin "1") (pinfunction "1_1") (pintype "passive"))
      (node (ref "R19") (pin "2") (pinfunction "2_2") (pintype "passive"))
      (node (ref "R20") (pin "2") (pinfunction "2_2") (pintype "passive"))
      (node (ref "R22") (pin "2") (pinfunction "2_2") (pintype "passive"))
      (node (ref "R23") (pin "2") (pinfunction "2_2") (pintype "passive"))
      (node (ref "R24") (pin "2") (pinfunction "2_2") (pintype "passive"))
      (node (ref "U1") (pin "2") (pinfunction "OUT_2") (pintype "power_in"))
      (node (ref "U1") (pin "4") (pinfunction "OUT_4") (pintype "power_in"))
      (node (ref "U3") (pin "10") (pinfunction "VDD_10") (pintype "bidirectional"))
      (node (ref "U3") (pin "11") (pinfunction "REGIN_11") (pintype "power_in"))
    )
    (net (code "37") (name "Net-(C3-Pad1)") (class "Default")
      (node (ref "C3") (pin "1") (pinfunction "1_1") (pintype "passive"))
      (node (ref "C4") (pin "2") (pinfunction "2_2") (pintype "passive"))
      (node (ref "T2") (pin "1") (pinfunction "1_1") (pintype "passive"))
      (node (ref "T2") (pin "5") (pinfunction "5_5") (pintype "passive"))
    )
    (net (code "38") (name "Net-(C5-Pad2)") (class "Default")
      (node (ref "C5") (pin "2") (pinfunction "2_2") (pintype "passive"))
      (node (ref "T3") (pin "1") (pinfunction "1_1") (pintype "passive"))
    )
    (net (code "39") (name "Net-(C13-Pad2)") (class "Default")
      (node (ref "C13") (pin "2") (pinfunction "2_2") (pintype "passive"))
      (node (ref "P3") (pin "3") (pinfunction "3_3") (pintype "passive"))
    )
    (net (code "40") (name "Net-(C14-Pad1)") (class "Default")
      (node (ref "C14") (pin "1") (pinfunction "1_1") (pintype "passive"))
      (node (ref "R2") (pin "1") (pinfunction "1_1") (pintype "passive"))
      (node (ref "R3") (pin "2") (pinfunction "2_2") (pintype "passive"))
    )
    (net (code "41") (name "Net-(C15-Pad1)") (class "Default")
      (node (ref "C15") (pin "1") (pinfunction "1_1") (pintype "passive"))
      (node (ref "P3") (pin "2") (pinfunction "2_2") (pintype "passive"))
    )
    (net (code "42") (name "Net-(C15-Pad2)") (class "Default")
      (node (ref "C15") (pin "2") (pinfunction "2_2") (pintype "passive"))
      (node (ref "R4") (pin "1") (pinfunction "1_1") (pintype "passive"))
    )
    (net (code "43") (name "Net-(C22-Pad1)") (class "Default")
      (node (ref "C22") (pin "1") (pinfunction "1_1") (pintype "passive"))
      (node (ref "P3") (pin "5") (pinfunction "5_5") (pintype "passive"))
    )
    (net (code "44") (name "Net-(C22-Pad2)") (class "Default")
      (node (ref "C22") (pin "2") (pinfunction "2_2") (pintype "passive"))
      (node (ref "R8") (pin "1") (pinfunction "1_1") (pintype "passive"))
    )
    (net (code "45") (name "Net-(C25-Pad2)") (class "Default")
      (node (ref "C25") (pin "2") (pinfunction "2_2") (pintype "passive"))
      (node (ref "P3") (pin "4") (pinfunction "4_4") (pintype "passive"))
    )
    (net (code "46") (name "Net-(C32-Pad1)") (class "Default")
      (node (ref "C32") (pin "1") (pinfunction "1_1") (pintype "passive"))
      (node (ref "J3") (pin "6") (pinfunction "SHLD_6") (pintype "passive"))
      (node (ref "J3") (pin "7") (pinfunction "SHLD_7") (pintype "passive"))
      (node (ref "J3") (pin "8") (pinfunction "SHLD_8") (pintype "passive"))
      (node (ref "J3") (pin "9") (pinfunction "SHLD_9") (pintype "passive"))
      (node (ref "R13") (pin "2") (pinfunction "2_2") (pintype "passive"))
    )
    (net (code "47") (name "Net-(C45-Pad2)") (class "Default")
      (node (ref "C45") (pin "2") (pinfunction "2_2") (pintype "passive"))
      (node (ref "P6") (pin "5") (pinfunction "5_5") (pintype "passive"))
      (node (ref "R22") (pin "1") (pinfunction "1_1") (pintype "passive"))
      (node (ref "R25") (pin "1") (pinfunction "1_1") (pintype "passive"))
    )
    (net (code "48") (name "Net-(D5-K)") (class "Default")
      (node (ref "D5") (pin "2") (pinfunction "K_2") (pintype "passive"))
      (node (ref "R26") (pin "2") (pinfunction "2_2") (pintype "passive"))
    )
    (net (code "49") (name "Net-(D6-K)") (class "Default")
      (node (ref "D6") (pin "2") (pinfunction "K_2") (pintype "passive"))
      (node (ref "R27") (pin "2") (pinfunction "2_2") (pintype "passive"))
    )
    (net (code "50") (name "Net-(D7-K)") (class "Default")
      (node (ref "D7") (pin "2") (pinfunction "K_2") (pintype "passive"))
      (node (ref "R28") (pin "2") (pinfunction "2_2") (pintype "passive"))
    )
    (net (code "51") (name "Net-(D8-K)") (class "Default")
      (node (ref "D8") (pin "2") (pinfunction "K_2") (pintype "passive"))
      (node (ref "R29") (pin "2") (pinfunction "2_2") (pintype "passive"))
    )
    (net (code "52") (name "Net-(D9-K)") (class "Default")
      (node (ref "D9") (pin "2") (pinfunction "K_2") (pintype "passive"))
      (node (ref "R30") (pin "2") (pinfunction "2_2") (pintype "passive"))
    )
    (net (code "53") (name "Net-(J1-Signal)") (class "Default")
      (node (ref "C4") (pin "1") (pinfunction "1_1") (pintype "passive"))
      (node (ref "J1") (pin "1") (pinfunction "Signal_1") (pintype "input"))
    )
    (net (code "54") (name "Net-(J2-Signal)") (class "Default")
      (node (ref "C5") (pin "1") (pinfunction "1_1") (pintype "passive"))
      (node (ref "C7") (pin "1") (pinfunction "1_1") (pintype "passive"))
      (node (ref "J2") (pin "1") (pinfunction "Signal_1") (pintype "input"))
    )
    (net (code "55") (name "Net-(J3-D+)") (class "Default")
      (node (ref "J3") (pin "3") (pinfunction "D+_3") (pintype "input"))
      (node (ref "R11") (pin "1") (pinfunction "1_1") (pintype "passive"))
    )
    (net (code "56") (name "Net-(J3-D-)") (class "Default")
      (node (ref "J3") (pin "2") (pinfunction "D-_2") (pintype "input"))
      (node (ref "R12") (pin "1") (pinfunction "1_1") (pintype "passive"))
    )
    (net (code "57") (name "Net-(P4-CHL)") (class "Default")
      (node (ref "C23") (pin "2") (pinfunction "2_2") (pintype "passive"))
      (node (ref "P4") (pin "1") (pinfunction "CHL_1") (pintype "passive"))
      (node (ref "R7") (pin "1") (pinfunction "1_1") (pintype "passive"))
    )
    (net (code "58") (name "Net-(P4-CHR)") (class "Default")
      (node (ref "C17") (pin "2") (pinfunction "2_2") (pintype "passive"))
      (node (ref "P4") (pin "2") (pinfunction "CHR_2") (pintype "passive"))
      (node (ref "R5") (pin "1") (pinfunction "1_1") (pintype "passive"))
    )
    (net (code "59") (name "Net-(Q1-D)") (class "Default")
      (node (ref "C19") (pin "2") (pinfunction "2_2") (pintype "passive"))
      (node (ref "Q1") (pin "2") (pinfunction "D_2") (pintype "passive"))
      (node (ref "R3") (pin "1") (pinfunction "1_1") (pintype "passive"))
    )
    (net (code "60") (name "Net-(Q1-G1)") (class "Default")
      (node (ref "Q1") (pin "4") (pinfunction "G1_4") (pintype "passive"))
      (node (ref "T3") (pin "5") (pinfunction "5_5") (pintype "passive"))
    )
    (net (code "61") (name "Net-(Q1-G2)") (class "Default")
      (node (ref "C20") (pin "1") (pinfunction "1_1") (pintype "passive"))
      (node (ref "Q1") (pin "3") (pinfunction "G2_3") (pintype "passive"))
      (node (ref "R6") (pin "1") (pinfunction "1_1") (pintype "passive"))
    )
    (net (code "62") (name "Net-(U2-BYPASS)") (class "Default")
      (node (ref "C18") (pin "2") (pinfunction "2_2") (pintype "passive"))
      (node (ref "C21") (pin "2") (pinfunction "2_2") (pintype "passive"))
      (node (ref "U2") (pin "3") (pinfunction "BYPASS_3") (pintype "passive"))
    )
    (net (code "63") (name "Net-(U2-INA)") (class "Default")
      (node (ref "C11") (pin "1") (pinfunction "1_1") (pintype "passive"))
      (node (ref "R1") (pin "1") (pinfunction "1_1") (pintype "passive"))
      (node (ref "R4") (pin "2") (pinfunction "2_2") (pintype "passive"))
      (node (ref "U2") (pin "2") (pinfunction "INA_2") (pintype "passive"))
    )
    (net (code "64") (name "Net-(U2-INB)") (class "Default")
      (node (ref "C26") (pin "1") (pinfunction "1_1") (pintype "passive"))
      (node (ref "R8") (pin "2") (pinfunction "2_2") (pintype "passive"))
      (node (ref "R9") (pin "2") (pinfunction "2_2") (pintype "passive"))
      (node (ref "U2") (pin "6") (pinfunction "INB_6") (pintype "passive"))
    )
    (net (code "65") (name "Net-(U2-OUTA)") (class "Default")
      (node (ref "C11") (pin "2") (pinfunction "2_2") (pintype "passive"))
      (node (ref "C12") (pin "1") (pinfunction "1_1") (pintype "passive"))
      (node (ref "C17") (pin "1") (pinfunction "1_1") (pintype "passive"))
      (node (ref "R1") (pin "2") (pinfunction "2_2") (pintype "passive"))
      (node (ref "U2") (pin "1") (pinfunction "OUTA_1") (pintype "passive"))
    )
    (net (code "66") (name "Net-(U2-OUTB)") (class "Default")
      (node (ref "C23") (pin "1") (pinfunction "1_1") (pintype "passive"))
      (node (ref "C24") (pin "1") (pinfunction "1_1") (pintype "passive"))
      (node (ref "C26") (pin "2") (pinfunction "2_2") (pintype "passive"))
      (node (ref "R9") (pin "1") (pinfunction "1_1") (pintype "passive"))
      (node (ref "U2") (pin "7") (pinfunction "OUTB_7") (pintype "passive"))
    )
    (net (code "67") (name "Net-(U2-VDD)") (class "Default")
      (node (ref "C10") (pin "2") (pinfunction "2_2") (pintype "passive"))
      (node (ref "C8") (pin "1") (pinfunction "1_1") (pintype "passive"))
      (node (ref "L2") (pin "2") (pinfunction "2_2") (pintype "passive"))
      (node (ref "U2") (pin "8") (pinfunction "VDD_8") (pintype "passive"))
    )
    (net (code "68") (name "RFGND") (class "Default")
      (node (ref "C1") (pin "1") (pinfunction "1_1") (pintype "passive"))
      (node (ref "C10") (pin "1") (pinfunction "1_1") (pintype "passive"))
      (node (ref "C12") (pin "2") (pinfunction "2_2") (pintype "passive"))
      (node (ref "C14") (pin "2") (pinfunction "2_2") (pintype "passive"))
      (node (ref "C16") (pin "1") (pinfunction "1_1") (pintype "passive"))
      (node (ref "C18") (pin "1") (pinfunction "1_1") (pintype "passive"))
      (node (ref "C2") (pin "1") (pinfunction "1_1") (pintype "passive"))
      (node (ref "C20") (pin "2") (pinfunction "2_2") (pintype "passive"))
      (node (ref "C21") (pin "1") (pinfunction "1_1") (pintype "passive"))
      (node (ref "C24") (pin "2") (pinfunction "2_2") (pintype "passive"))
      (node (ref "C27") (pin "1") (pinfunction "1_1") (pintype "passive"))
      (node (ref "C28") (pin "1") (pinfunction "1_1") (pintype "passive"))
      (node (ref "C29") (pin "1") (pinfunction "1_1") (pintype "passive"))
      (node (ref "C30") (pin "1") (pinfunction "1_1") (pintype "passive"))
      (node (ref "C31") (pin "2") (pinfunction "2_2") (pintype "passive"))
      (node (ref "C32") (pin "2") (pinfunction "2_2") (pintype "passive"))
      (node (ref "C33") (pin "1") (pinfunction "1_1") (pintype "passive"))
      (node (ref "C34") (pin "2") (pinfunction "2_2") (pintype "passive"))
      (node (ref "C35") (pin "2") (pinfunction "2_2") (pintype "passive"))
      (node (ref "C36") (pin "2") (pinfunction "2_2") (pintype "passive"))
      (node (ref "C37") (pin "2") (pinfunction "2_2") (pintype "passive"))
      (node (ref "C38") (pin "2") (pinfunction "2_2") (pintype "passive"))
      (node (ref "C40") (pin "2") (pinfunction "2_2") (pintype "passive"))
      (node (ref "C41") (pin "2") (pinfunction "2_2") (pintype "passive"))
      (node (ref "C44") (pin "1") (pinfunction "1_1") (pintype "passive"))
      (node (ref "C45") (pin "1") (pinfunction "1_1") (pintype "passive"))
      (node (ref "C7") (pin "2") (pinfunction "2_2") (pintype "passive"))
      (node (ref "C8") (pin "2") (pinfunction "2_2") (pintype "passive"))
      (node (ref "C9") (pin "1") (pinfunction "1_1") (pintype "passive"))
      (node (ref "D1") (pin "2") (pinfunction "K_2") (pintype "passive"))
      (node (ref "D2") (pin "1") (pinfunction "A_1") (pintype "passive"))
      (node (ref "D3") (pin "2") (pinfunction "K_2") (pintype "passive"))
      (node (ref "D4") (pin "1") (pinfunction "A_1") (pintype "passive"))
      (node (ref "J1") (pin "2") (pinfunction "GND_2") (pintype "power_in"))
      (node (ref "J2") (pin "2") (pinfunction "GND_2") (pintype "power_in"))
      (node (ref "J2") (pin "3") (pinfunction "GND_3") (pintype "power_in"))
      (node (ref "J2") (pin "4") (pinfunction "GND_4") (pintype "power_in"))
      (node (ref "J2") (pin "5") (pinfunction "GND_5") (pintype "power_in"))
      (node (ref "J3") (pin "4") (pinfunction "GND_4") (pintype "power_in"))
      (node (ref "K1") (pin "1") (pinfunction "1_1") (pintype "passive"))
      (node (ref "K2") (pin "1") (pinfunction "1_1") (pintype "passive"))
      (node (ref "K3") (pin "1") (pinfunction "1_1") (pintype "passive"))
      (node (ref "K4") (pin "1") (pinfunction "1_1") (pintype "passive"))
      (node (ref "P1") (pin "3") (pinfunction "COM_3") (pintype "passive"))
      (node (ref "P2") (pin "1") (pinfunction "1_1") (pintype "passive"))
      (node (ref "P3") (pin "1") (pinfunction "1_1") (pintype "passive"))
      (node (ref "P3") (pin "6") (pinfunction "6_6") (pintype "passive"))
      (node (ref "P4") (pin "3") (pinfunction "COM_3") (pintype "passive"))
      (node (ref "P5") (pin "2") (pinfunction "2_2") (pintype "passive"))
      (node (ref "P6") (pin "2") (pinfunction "2_2") (pintype "passive"))
      (node (ref "P6") (pin "3") (pinfunction "3_3") (pintype "passive"))
      (node (ref "P6") (pin "9") (pinfunction "9_9") (pintype "passive"))
      (node (ref "Q1") (pin "1") (pinfunction "S_1") (pintype "passive"))
      (node (ref "R13") (pin "1") (pinfunction "1_1") (pintype "passive"))
      (node (ref "R14") (pin "1") (pinfunction "1_1") (pintype "passive"))
      (node (ref "R18") (pin "2") (pinfunction "BOT_2") (pintype "passive"))
      (node (ref "R5") (pin "2") (pinfunction "2_2") (pintype "passive"))
      (node (ref "R7") (pin "2") (pinfunction "2_2") (pintype "passive"))
      (node (ref "T1") (pin "2") (pinfunction "2_2") (pintype "passive"))
      (node (ref "T1") (pin "3") (pinfunction "3_3") (pintype "passive"))
      (node (ref "T1") (pin "6") (pinfunction "6_6") (pintype "passive"))
      (node (ref "T1") (pin "7") (pinfunction "7_7") (pintype "passive"))
      (node (ref "T2") (pin "2") (pinfunction "2_2") (pintype "passive"))
      (node (ref "T2") (pin "3") (pinfunction "3_3") (pintype "passive"))
      (node (ref "T2") (pin "6") (pinfunction "6_6") (pintype "passive"))
      (node (ref "T2") (pin "7") (pinfunction "7_7") (pintype "passive"))
      (node (ref "T3") (pin "2") (pinfunction "2_2") (pintype "passive"))
      (node (ref "T3") (pin "3") (pinfunction "3_3") (pintype "passive"))
      (node (ref "T3") (pin "6") (pinfunction "6_6") (pintype "passive"))
      (node (ref "T3") (pin "7") (pinfunction "7_7") (pintype "passive"))
      (node (ref "U1") (pin "1") (pinfunction "GND_1") (pintype "power_in"))
      (node (ref "U2") (pin "4") (pinfunction "GND_4") (pintype "passive"))
      (node (ref "U3") (pin "7") (pinfunction "GND_7") (pintype "bidirectional"))
      (node (ref "U4") (pin "10") (pinfunction "NC_10") (pintype "passive"))
      (node (ref "U4") (pin "11") (pinfunction "NC_11") (pintype "passive"))
      (node (ref "U4") (pin "13") (pinfunction "GND_13") (pintype "passive"))
      (node (ref "U4") (pin "14") (pinfunction "GND_14") (pintype "passive"))
      (node (ref "U4") (pin "9") (pinfunction "RFGND_9") (pintype "passive"))
      (node (ref "Z1") (pin "2") (pinfunction "Vn_2") (pintype "power_in"))
    )
    (net (code "69") (name "RFVCC") (class "Default")
      (node (ref "C16") (pin "2") (pinfunction "2_2") (pintype "passive"))
      (node (ref "C2") (pin "2") (pinfunction "2_2") (pintype "passive"))
      (node (ref "C39") (pin "2") (pinfunction "2_2") (pintype "passive"))
      (node (ref "C42") (pin "2") (pinfunction "2_2") (pintype "passive"))
      (node (ref "C43") (pin "2") (pinfunction "2_2") (pintype "passive"))
      (node (ref "C44") (pin "2") (pinfunction "2_2") (pintype "passive"))
      (node (ref "L1") (pin "2") (pinfunction "2_2") (pintype "passive"))
      (node (ref "R2") (pin "2") (pinfunction "2_2") (pintype "passive"))
      (node (ref "R21") (pin "2") (pinfunction "2_2") (pintype "passive"))
      (node (ref "R6") (pin "2") (pinfunction "2_2") (pintype "passive"))
      (node (ref "U4") (pin "20") (pinfunction "VDD1_20") (pintype "passive"))
      (node (ref "U4") (pin "21") (pinfunction "VDD2_21") (pintype "passive"))
      (node (ref "U4") (pin "5") (pinfunction "BAND_5") (pintype "passive"))
    )
    (net (code "70") (name "VBUS") (class "Default")
      (node (ref "C33") (pin "2") (pinfunction "2_2") (pintype "passive"))
      (node (ref "C34") (pin "1") (pinfunction "1_1") (pintype "passive"))
      (node (ref "C9") (pin "2") (pinfunction "2_2") (pintype "passive"))
      (node (ref "L2") (pin "1") (pinfunction "1_1") (pintype "passive"))
      (node (ref "L3") (pin "2") (pinfunction "2_2") (pintype "passive"))
      (node (ref "U1") (pin "3") (pinfunction "IN_3") (pintype "power_in"))
      (node (ref "U3") (pin "12") (pinfunction "VBUS_12") (pintype "input"))
      (node (ref "Z1") (pin "5") (pinfunction "Vp_5") (pintype "power_in"))
    )
    (net (code "71") (name "VUSB") (class "Default")
      (node (ref "C35") (pin "1") (pinfunction "1_1") (pintype "passive"))
      (node (ref "J3") (pin "1") (pinfunction "VBUS_1") (pintype "power_in"))
      (node (ref "L3") (pin "1") (pinfunction "1_1") (pintype "passive"))
    )
    (net (code "72") (name "unconnected-(J1-GND-Pad3)") (class "Default")
      (node (ref "J1") (pin "3") (pinfunction "GND_3") (pintype "power_in"))
    )
    (net (code "73") (name "unconnected-(J1-GND-Pad4)") (class "Default")
      (node (ref "J1") (pin "4") (pinfunction "GND_4") (pintype "power_in"))
    )
    (net (code "74") (name "unconnected-(J1-GND-Pad5)") (class "Default")
      (node (ref "J1") (pin "5") (pinfunction "GND_5") (pintype "power_in"))
    )
    (net (code "75") (name "unconnected-(J3-SHLD-Pad5)") (class "Default")
      (node (ref "J3") (pin "5") (pinfunction "SHLD_5") (pintype "passive+no_connect"))
    )
    (net (code "76") (name "unconnected-(P1-CHL-Pad1)") (class "Default")
      (node (ref "P1") (pin "1") (pinfunction "CHL_1") (pintype "passive+no_connect"))
    )
    (net (code "77") (name "unconnected-(P6-Pad6)") (class "Default")
      (node (ref "P6") (pin "6") (pinfunction "6_6") (pintype "passive+no_connect"))
    )
    (net (code "78") (name "unconnected-(P6-Pad8)") (class "Default")
      (node (ref "P6") (pin "8") (pinfunction "8_8") (pintype "passive+no_connect"))
    )
    (net (code "79") (name "unconnected-(P6-Pad10)") (class "Default")
      (node (ref "P6") (pin "10") (pinfunction "10_10") (pintype "passive+no_connect"))
    )
    (net (code "80") (name "unconnected-(T1-Pad4)") (class "Default")
      (node (ref "T1") (pin "4") (pinfunction "4_4") (pintype "passive+no_connect"))
    )
    (net (code "81") (name "unconnected-(T2-Pad4)") (class "Default")
      (node (ref "T2") (pin "4") (pinfunction "4_4") (pintype "passive+no_connect"))
    )
    (net (code "82") (name "unconnected-(T3-Pad4)") (class "Default")
      (node (ref "T3") (pin "4") (pinfunction "4_4") (pintype "passive+no_connect"))
    )
    (net (code "83") (name "unconnected-(U3-P0.0-Pad6)") (class "Default")
      (node (ref "U3") (pin "6") (pinfunction "P0.0_6") (pintype "power_in+no_connect"))
    )
    (net (code "84") (name "unconnected-(U3-P0.1-Pad5)") (class "Default")
      (node (ref "U3") (pin "5") (pinfunction "P0.1_5") (pintype "power_in+no_connect"))
    )
    (net (code "85") (name "unconnected-(U3-P0.2-Pad4)") (class "Default")
      (node (ref "U3") (pin "4") (pinfunction "P0.2_4") (pintype "bidirectional+no_connect"))
    )
    (net (code "86") (name "unconnected-(U3-P0.3-Pad3)") (class "Default")
      (node (ref "U3") (pin "3") (pinfunction "P0.3_3") (pintype "bidirectional+no_connect"))
    )
    (net (code "87") (name "unconnected-(U3-P2.2-Pad36)") (class "Default")
      (node (ref "U3") (pin "36") (pinfunction "P2.2_36") (pintype "bidirectional+no_connect"))
    )
    (net (code "88") (name "unconnected-(U3-P2.3-Pad35)") (class "Default")
      (node (ref "U3") (pin "35") (pinfunction "P2.3_35") (pintype "bidirectional+no_connect"))
    )
    (net (code "89") (name "unconnected-(U3-P2.4-Pad34)") (class "Default")
      (node (ref "U3") (pin "34") (pinfunction "P2.4_34") (pintype "bidirectional+no_connect"))
    )
    (net (code "90") (name "unconnected-(U3-P2.5-Pad33)") (class "Default")
      (node (ref "U3") (pin "33") (pinfunction "P2.5_33") (pintype "bidirectional+no_connect"))
    )
    (net (code "91") (name "unconnected-(U3-P2.6-Pad32)") (class "Default")
      (node (ref "U3") (pin "32") (pinfunction "P2.6_32") (pintype "power_in+no_connect"))
    )
    (net (code "92") (name "unconnected-(U3-P2.7-Pad31)") (class "Default")
      (node (ref "U3") (pin "31") (pinfunction "P2.7_31") (pintype "power_in"))
    )
    (net (code "93") (name "unconnected-(U3-P3.6-Pad24)") (class "Default")
      (node (ref "U3") (pin "24") (pinfunction "P3.6_24") (pintype "bidirectional+no_connect"))
    )
    (net (code "94") (name "unconnected-(U3-P3.7-Pad23)") (class "Default")
      (node (ref "U3") (pin "23") (pinfunction "P3.7_23") (pintype "bidirectional+no_connect"))
    )
    (net (code "95") (name "unconnected-(U3-P4.0-Pad22)") (class "Default")
      (node (ref "U3") (pin "22") (pinfunction "P4.0_22") (pintype "bidirectional+no_connect"))
    )
    (net (code "96") (name "unconnected-(U3-P4.1-Pad21)") (class "Default")
      (node (ref "U3") (pin "21") (pinfunction "P4.1_21") (pintype "bidirectional+no_connect"))
    )
    (net (code "97") (name "unconnected-(U3-P4.2-Pad20)") (class "Default")
      (node (ref "U3") (pin "20") (pinfunction "P4.2_20") (pintype "bidirectional+no_connect"))
    )
    (net (code "98") (name "unconnected-(U3-P4.3-Pad19)") (class "Default")
      (node (ref "U3") (pin "19") (pinfunction "P4.3_19") (pintype "bidirectional+no_connect"))
    )
    (net (code "99") (name "unconnected-(U3-P4.4-Pad18)") (class "Default")
      (node (ref "U3") (pin "18") (pinfunction "P4.4_18") (pintype "bidirectional+no_connect"))
    )
    (net (code "100") (name "unconnected-(U3-P4.5-Pad17)") (class "Default")
      (node (ref "U3") (pin "17") (pinfunction "P4.5_17") (pintype "bidirectional+no_connect"))
    )
    (net (code "101") (name "unconnected-(U3-P4.6-Pad16)") (class "Default")
      (node (ref "U3") (pin "16") (pinfunction "P4.6_16") (pintype "bidirectional+no_connect"))
    )
    (net (code "102") (name "unconnected-(U3-P4.7-Pad15)") (class "Default")
      (node (ref "U3") (pin "15") (pinfunction "P4.7_15") (pintype "bidirectional+no_connect"))
    )
    (net (code "103") (name "unconnected-(U4-NC-Pad6)") (class "Default")
      (node (ref "U4") (pin "6") (pinfunction "NC_6") (pintype "passive+no_connect"))
    )
    (net (code "104") (name "unconnected-(U4-NC-Pad7)") (class "Default")
      (node (ref "U4") (pin "7") (pinfunction "NC_7") (pintype "passive+no_connect"))
    )
    (net (code "105") (name "unconnected-(Z1-I{slash}O-Pad4)") (class "Default")
      (node (ref "Z1") (pin "4") (pinfunction "I/O_4") (pintype "passive+no_connect"))
    )
    (net (code "106") (name "unconnected-(Z1-I{slash}O-Pad6)") (class "Default")
      (node (ref "Z1") (pin "6") (pinfunction "I/O_6") (pintype "passive+no_connect"))
    )
  )
)
